# Lamp.net
KiCad netlist of a schematic drawn in EasyEDA
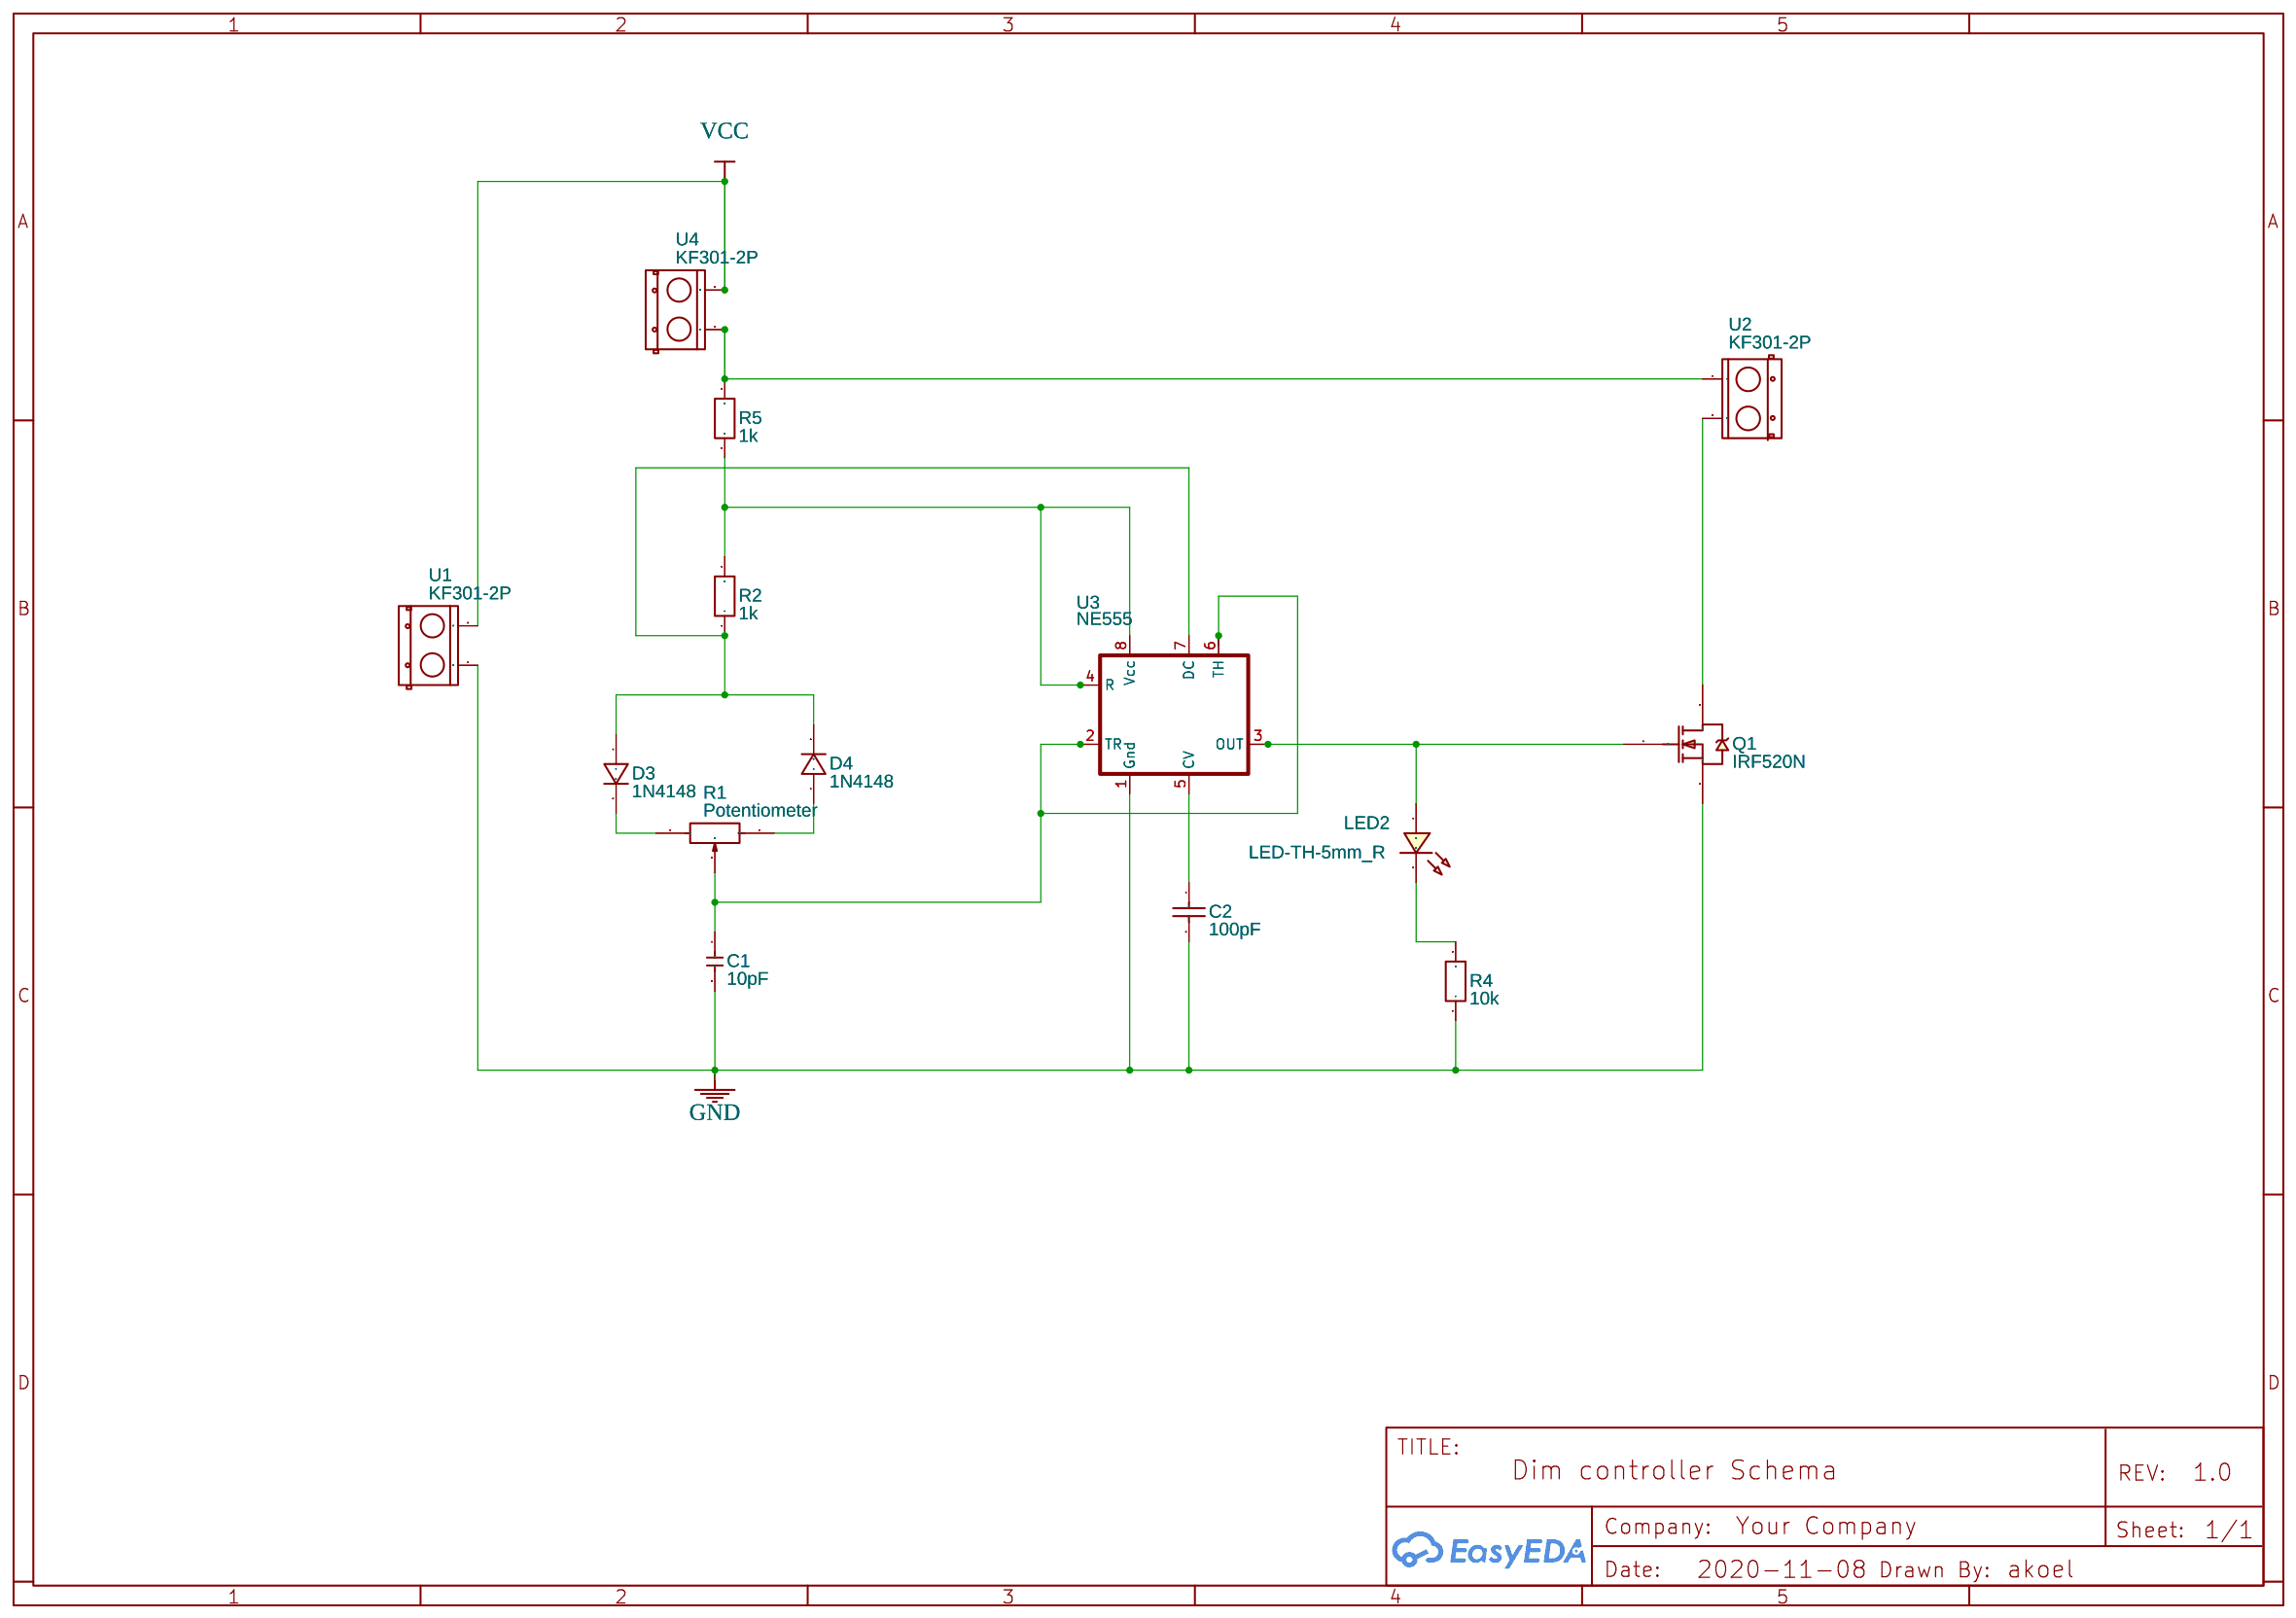
[diagram p0: schematic sheet]

(export (version "E")
  (design (tool "Eeschema 10.0.6"))
  (components
    (comp (ref "C1")
      (value "10pF")
      (fields
        (field (name "BOM_Manufacturer Part") "CC1-F5SL2A101KSPW")
        (field (name "BOM_Supplier Part") "302010208")
      )
      (libsource (lib "") (part "10pF"))
    )
    (comp (ref "C2")
      (value "100pF")
      (fields
        (field (name "BOM_Manufacturer Part") "100PF/50V10%")
        (field (name "BOM_Supplier Part") "C9339")
      )
      (libsource (lib "") (part "100pF"))
    )
    (comp (ref "D3")
      (value "1N4148")
      (fields (field (name "BOM_Supplier Part") "C14516"))
      (libsource (lib "") (part "1N4148_1"))
    )
    (comp (ref "D4")
      (value "1N4148")
      (fields (field (name "BOM_Supplier Part") "C14516"))
      (libsource (lib "") (part "1N4148"))
    )
    (comp (ref "LED2")
      (value "LED-TH-5mm_R")
      (fields
        (field (name "BOM_Manufacturer Part") "204-10SDRD/S530-A3-L")
        (field (name "BOM_Supplier Part") "C84774")
      )
      (libsource (lib "") (part "LED-TH-3mm_R"))
    )
    (comp (ref "Q1") (value "IRF520N") (libsource (lib "") (part "IRF520N")))
    (comp (ref "R1") (value "Potentiometer") (libsource (lib "") (part "Potentiometer")))
    (comp (ref "R2") (value "1k") (libsource (lib "") (part "R_AXIAL-0.4_EU_1")))
    (comp (ref "R4") (value "10k") (libsource (lib "") (part "R_AXIAL-0.4_EU_1")))
    (comp (ref "R5") (value "1k") (libsource (lib "") (part "R_AXIAL-0.4_EU")))
    (comp (ref "U1")
      (value "KF301-2P")
      (fields (field (name "BOM_Manufacturer Part") "KF301"))
      (libsource (lib "") (part "KF301-2P"))
    )
    (comp (ref "U2")
      (value "KF301-2P")
      (fields (field (name "BOM_Manufacturer Part") "KF301"))
      (libsource (lib "") (part "KF301-2P_1"))
    )
    (comp (ref "U3") (value "NE555") (libsource (lib "") (part "NE555")))
    (comp (ref "U4")
      (value "KF301-2P")
      (fields (field (name "BOM_Manufacturer Part") "KF301"))
      (libsource (lib "") (part "KF301-2P_2"))
    )
  )
  (nets
    (net (code "1") (name "GND") (class "Default")
      (node (ref "C1") (pin "2") (pinfunction "2_2") (pintype "unspecified"))
      (node (ref "C2") (pin "2") (pinfunction "2_2") (pintype "input"))
      (node (ref "Q1") (pin "3") (pinfunction "S_3") (pintype "unspecified"))
      (node (ref "R4") (pin "1") (pinfunction "1_1") (pintype "unspecified"))
      (node (ref "U1") (pin "1") (pinfunction "1_1") (pintype "unspecified"))
      (node (ref "U3") (pin "1") (pinfunction "Gnd_1") (pintype "unspecified"))
    )
    (net (code "2") (name "Net-(D3-Pad2)") (class "Default")
      (node (ref "D3") (pin "2") (pinfunction "2_2") (pintype "unspecified"))
      (node (ref "R1") (pin "3") (pinfunction "3_3") (pintype "unspecified"))
    )
    (net (code "3") (name "Net-(D4-Pad1)") (class "Default")
      (node (ref "D4") (pin "1") (pinfunction "1_1") (pintype "unspecified"))
      (node (ref "R1") (pin "1") (pinfunction "1_1") (pintype "unspecified"))
    )
    (net (code "4") (name "Net-(LED2-Pad2)") (class "Default")
      (node (ref "LED2") (pin "2") (pinfunction "2_2") (pintype "unspecified"))
      (node (ref "R4") (pin "2") (pinfunction "2_2") (pintype "unspecified"))
    )
    (net (code "5") (name "Net-(Q1-D)") (class "Default")
      (node (ref "Q1") (pin "2") (pinfunction "D_2") (pintype "unspecified"))
      (node (ref "U2") (pin "2") (pinfunction "2_2") (pintype "unspecified"))
    )
    (net (code "6") (name "Net-(Q1-G)") (class "Default")
      (node (ref "LED2") (pin "1") (pinfunction "1_1") (pintype "unspecified"))
      (node (ref "Q1") (pin "1") (pinfunction "G_1") (pintype "unspecified"))
      (node (ref "U3") (pin "3") (pinfunction "OUT_3") (pintype "unspecified"))
    )
    (net (code "7") (name "Net-(R5-Pad1)") (class "Default")
      (node (ref "R5") (pin "1") (pinfunction "1_1") (pintype "unspecified"))
      (node (ref "U2") (pin "1") (pinfunction "1_1") (pintype "unspecified"))
      (node (ref "U4") (pin "1") (pinfunction "1_1") (pintype "unspecified"))
    )
    (net (code "8") (name "Net-(U3-CV)") (class "Default")
      (node (ref "C2") (pin "1") (pinfunction "1_1") (pintype "input"))
      (node (ref "U3") (pin "5") (pinfunction "CV_5") (pintype "unspecified"))
    )
    (net (code "9") (name "Net-(U3-DC)") (class "Default")
      (node (ref "D3") (pin "1") (pinfunction "1_1") (pintype "unspecified"))
      (node (ref "D4") (pin "2") (pinfunction "2_2") (pintype "unspecified"))
      (node (ref "R2") (pin "1") (pinfunction "1_1") (pintype "unspecified"))
      (node (ref "U3") (pin "7") (pinfunction "DC_7") (pintype "unspecified"))
    )
    (net (code "10") (name "Net-(U3-R)") (class "Default")
      (node (ref "R2") (pin "2") (pinfunction "2_2") (pintype "unspecified"))
      (node (ref "R5") (pin "2") (pinfunction "2_2") (pintype "unspecified"))
      (node (ref "U3") (pin "4") (pinfunction "R_4") (pintype "unspecified"))
      (node (ref "U3") (pin "8") (pinfunction "Vcc_8") (pintype "unspecified"))
    )
    (net (code "11") (name "Net-(U3-TH)") (class "Default")
      (node (ref "C1") (pin "1") (pinfunction "1_1") (pintype "unspecified"))
      (node (ref "R1") (pin "2") (pinfunction "2_2") (pintype "unspecified"))
      (node (ref "U3") (pin "2") (pinfunction "TR_2") (pintype "unspecified"))
      (node (ref "U3") (pin "6") (pinfunction "TH_6") (pintype "unspecified"))
    )
    (net (code "12") (name "VCC") (class "Default")
      (node (ref "U1") (pin "2") (pinfunction "2_2") (pintype "unspecified"))
      (node (ref "U4") (pin "2") (pinfunction "2_2") (pintype "unspecified"))
    )
  )
)
